# mcu_base.net
KiCad netlist of a schematic drawn in Altium Designer
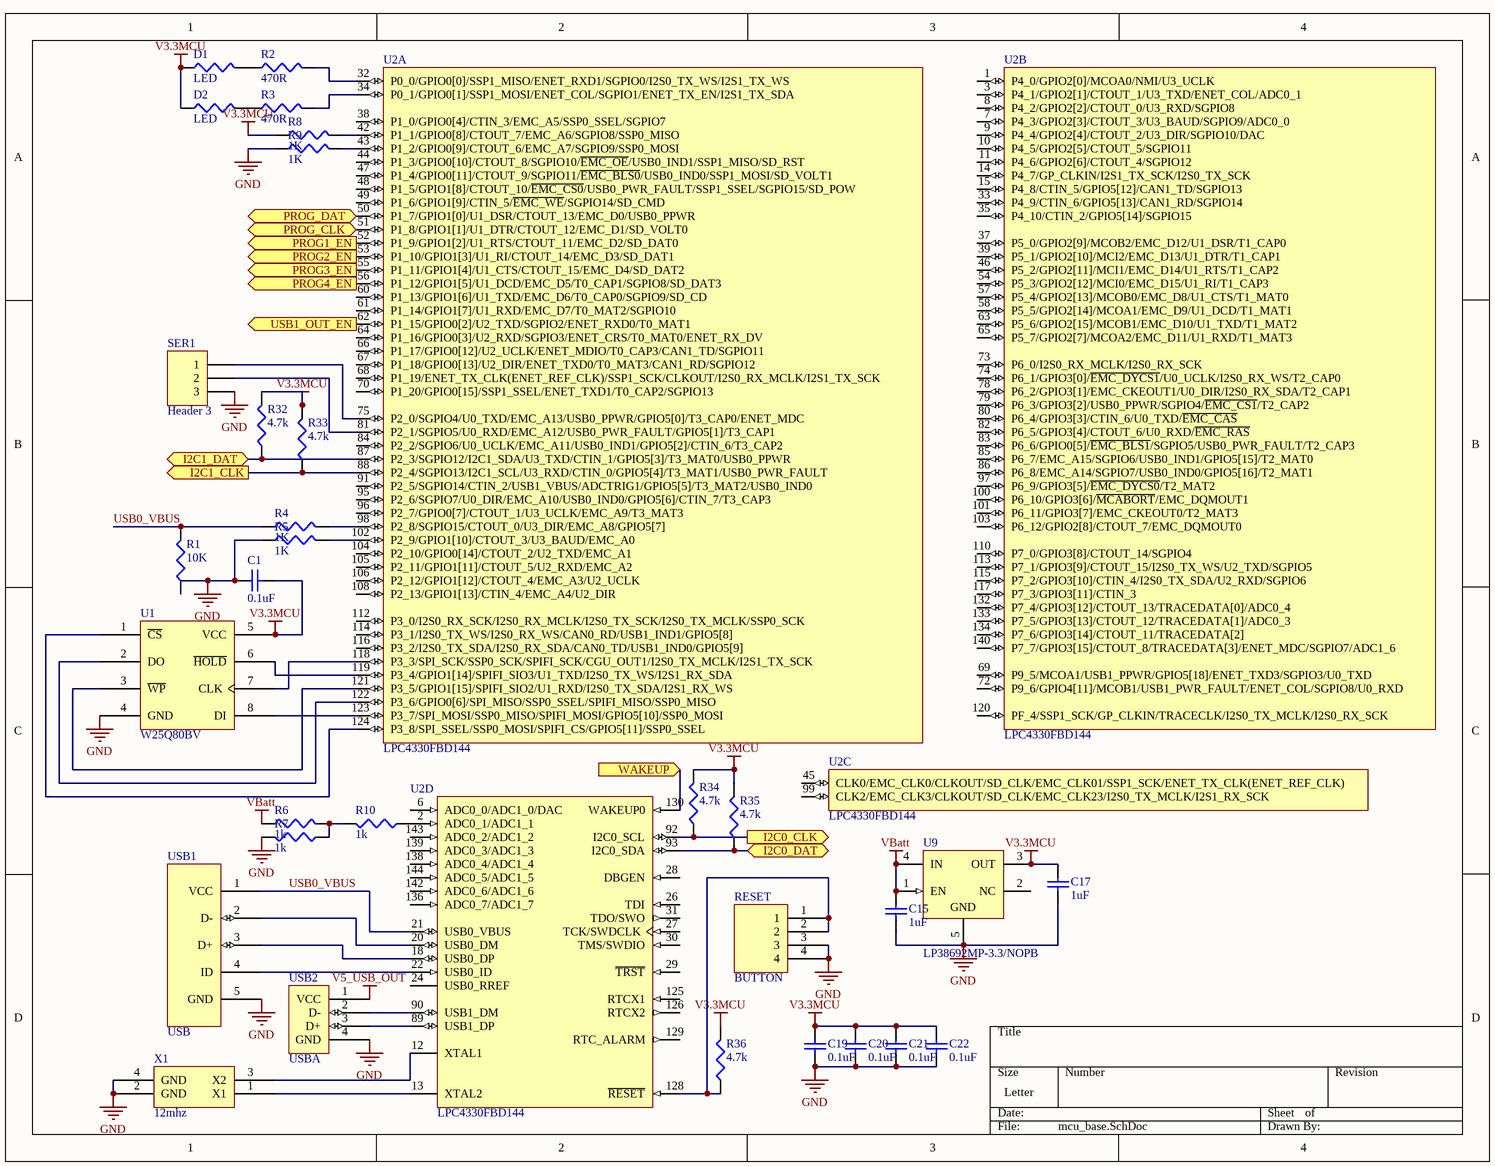
[diagram p0: mcu_base.SchDoc]

(export (version "E")
  (design (tool "Eeschema 10.0.6"))
  (components
    (comp (ref "C1")
      (value "0.1uF")
      (footprint "1608[0603]")
      (description "Capacitor (Semiconductor SIM Model)")
      (fields (field (name "PUBLISHER") "Altium Limited"))
      (libsource (lib "Miscellaneous Devices") (part "Cap Semi"))
    )
    (comp (ref "C15")
      (value "1uF")
      (footprint "1608[0603]")
      (description "Capacitor (Semiconductor SIM Model)")
      (fields (field (name "PUBLISHER") "Altium Limited"))
      (libsource (lib "Miscellaneous Devices") (part "Cap Semi"))
    )
    (comp (ref "C17")
      (value "1uF")
      (footprint "1608[0603]")
      (description "Capacitor (Semiconductor SIM Model)")
      (fields (field (name "PUBLISHER") "Altium Limited"))
      (libsource (lib "Miscellaneous Devices") (part "Cap Semi"))
    )
    (comp (ref "C19")
      (value "0.1uF")
      (footprint "1608[0603]")
      (description "Capacitor (Semiconductor SIM Model)")
      (fields (field (name "PUBLISHER") "Altium Limited"))
      (libsource (lib "Miscellaneous Devices") (part "Cap Semi"))
    )
    (comp (ref "C20")
      (value "0.1uF")
      (footprint "1608[0603]")
      (description "Capacitor (Semiconductor SIM Model)")
      (fields (field (name "PUBLISHER") "Altium Limited"))
      (libsource (lib "Miscellaneous Devices") (part "Cap Semi"))
    )
    (comp (ref "C21")
      (value "0.1uF")
      (footprint "1608[0603]")
      (description "Capacitor (Semiconductor SIM Model)")
      (fields (field (name "PUBLISHER") "Altium Limited"))
      (libsource (lib "Miscellaneous Devices") (part "Cap Semi"))
    )
    (comp (ref "C22")
      (value "0.1uF")
      (footprint "1608[0603]")
      (description "Capacitor (Semiconductor SIM Model)")
      (fields (field (name "PUBLISHER") "Altium Limited"))
      (libsource (lib "Miscellaneous Devices") (part "Cap Semi"))
    )
    (comp (ref "D1")
      (value "LED")
      (footprint "J1-0603")
      (description "Resistor")
      (fields (field (name "PUBLISHER") "Altium Limited"))
      (libsource (lib "Miscellaneous Devices") (part "Res3"))
    )
    (comp (ref "D2")
      (value "LED")
      (footprint "J1-0603")
      (description "Resistor")
      (fields (field (name "PUBLISHER") "Altium Limited"))
      (libsource (lib "Miscellaneous Devices") (part "Res3"))
    )
    (comp (ref "R1")
      (value "10K")
      (footprint "J1-0603")
      (description "Resistor")
      (fields (field (name "PUBLISHER") "Altium Limited"))
      (libsource (lib "Miscellaneous Devices") (part "Res3"))
    )
    (comp (ref "R2")
      (value "470R")
      (footprint "J1-0603")
      (description "Resistor")
      (fields (field (name "PUBLISHER") "Altium Limited"))
      (libsource (lib "Miscellaneous Devices") (part "Res3"))
    )
    (comp (ref "R3")
      (value "470R")
      (footprint "J1-0603")
      (description "Resistor")
      (fields (field (name "PUBLISHER") "Altium Limited"))
      (libsource (lib "Miscellaneous Devices") (part "Res3"))
    )
    (comp (ref "R4")
      (value "1K")
      (footprint "J1-0603")
      (description "Resistor")
      (fields (field (name "PUBLISHER") "Altium Limited"))
      (libsource (lib "Miscellaneous Devices") (part "Res3"))
    )
    (comp (ref "R5")
      (value "1K")
      (footprint "J1-0603")
      (description "Resistor")
      (fields (field (name "PUBLISHER") "Altium Limited"))
      (libsource (lib "Miscellaneous Devices") (part "Res3"))
    )
    (comp (ref "R6")
      (value "1k")
      (footprint "J1-0603")
      (description "Resistor")
      (fields (field (name "PUBLISHER") "Altium Limited"))
      (libsource (lib "Miscellaneous Devices") (part "Res3"))
    )
    (comp (ref "R7")
      (value "1k")
      (footprint "J1-0603")
      (description "Resistor")
      (fields (field (name "PUBLISHER") "Altium Limited"))
      (libsource (lib "Miscellaneous Devices") (part "Res3"))
    )
    (comp (ref "R8")
      (value "1K")
      (footprint "J1-0603")
      (description "Resistor")
      (fields (field (name "PUBLISHER") "Altium Limited"))
      (libsource (lib "Miscellaneous Devices") (part "Res3"))
    )
    (comp (ref "R9")
      (value "1K")
      (footprint "J1-0603")
      (description "Resistor")
      (fields (field (name "PUBLISHER") "Altium Limited"))
      (libsource (lib "Miscellaneous Devices") (part "Res3"))
    )
    (comp (ref "R10")
      (value "1k")
      (footprint "J1-0603")
      (description "Resistor")
      (fields (field (name "PUBLISHER") "Altium Limited"))
      (libsource (lib "Miscellaneous Devices") (part "Res3"))
    )
    (comp (ref "R32")
      (value "4.7k")
      (footprint "J1-0603")
      (description "Resistor")
      (fields (field (name "PUBLISHER") "Altium Limited"))
      (libsource (lib "Miscellaneous Devices") (part "Res3"))
    )
    (comp (ref "R33")
      (value "4.7k")
      (footprint "J1-0603")
      (description "Resistor")
      (fields (field (name "PUBLISHER") "Altium Limited"))
      (libsource (lib "Miscellaneous Devices") (part "Res3"))
    )
    (comp (ref "R34")
      (value "4.7k")
      (footprint "J1-0603")
      (description "Resistor")
      (fields (field (name "PUBLISHER") "Altium Limited"))
      (libsource (lib "Miscellaneous Devices") (part "Res3"))
    )
    (comp (ref "R35")
      (value "4.7k")
      (footprint "J1-0603")
      (description "Resistor")
      (fields (field (name "PUBLISHER") "Altium Limited"))
      (libsource (lib "Miscellaneous Devices") (part "Res3"))
    )
    (comp (ref "R36")
      (value "4.7k")
      (footprint "J1-0603")
      (description "Resistor")
      (fields (field (name "PUBLISHER") "Altium Limited"))
      (libsource (lib "Miscellaneous Devices") (part "Res3"))
    )
    (comp (ref "RESET")
      (value "BUTTON")
      (footprint "B3FS_SWITCH")
      (libsource (lib "custom_for_quadrotor") (part "BUTTON"))
    )
    (comp (ref "SER1")
      (value "Header 3")
      (footprint "HDR1X3")
      (description "Header, 3-Pin")
      (fields (field (name "PUBLISHER") "Altium Limited"))
      (libsource (lib "Miscellaneous Connectors") (part "Header 3"))
    )
    (comp (ref "U1") (value "W25Q80BV") (footprint "D8_N") (libsource (lib "KyliesParts") (part "W25Q80BV")))
    (comp (ref "U2")
      (value "LPC4330FBD144")
      (footprint "SOT486-1_V")
      (libsource (lib "NXP Semiconductors Cortex-M4") (part "LPC4330FBD144"))
    )
    (comp (ref "U9")
      (value "LP38692MP-3.3/NOPB")
      (footprint "MP05A_N")
      (fields (field (name "MANUFACTURER") "National Semiconductor"))
      (libsource (lib "National Semiconductor LDO") (part "LP38692MP-3.3/NOPB"))
    )
    (comp (ref "USB1")
      (value "USB")
      (footprint "USB/SM0.8-6H5")
      (libsource (lib "custom_for_quadrotor") (part "USB"))
    )
    (comp (ref "USB2")
      (value "USBA")
      (footprint "USB2.5-2V4A")
      (libsource (lib "custom_for_quadrotor") (part "USBA"))
    )
    (comp (ref "X1")
      (value "12mhz")
      (footprint "2SMX-3SMXB")
      (libsource (lib "KyliesParts") (part "crystal"))
    )
  )
  (nets
    (net (code "1") (name "/I2C0_CLK") (class "Default")
      (node (ref "R34") (pin "1") (pinfunction "1_1") (pintype "passive"))
      (node (ref "U2") (pin "92") (pinfunction "I2C0_SCL_92") (pintype "bidirectional"))
    )
    (net (code "2") (name "/I2C0_DAT") (class "Default")
      (node (ref "R35") (pin "1") (pinfunction "1_1") (pintype "passive"))
      (node (ref "U2") (pin "93") (pinfunction "I2C0_SDA_93") (pintype "bidirectional"))
    )
    (net (code "3") (name "/I2C1_CLK") (class "Default")
      (node (ref "R33") (pin "1") (pinfunction "1_1") (pintype "passive"))
      (node (ref "U2") (pin "88") (pinfunction "P2_4/SGPIO13/I2C1_SCL/U3_RXD/CTIN_0/GPIO5[4]/T3_MAT1/USB0_PWR_FAULT_88") (pintype "bidirectional"))
    )
    (net (code "4") (name "/I2C1_DAT") (class "Default")
      (node (ref "R32") (pin "1") (pinfunction "1_1") (pintype "passive"))
      (node (ref "U2") (pin "87") (pinfunction "P2_3/SGPIO12/I2C1_SDA/U3_TXD/CTIN_1/GPIO5[3]/T3_MAT0/USB0_PPWR_87") (pintype "bidirectional"))
    )
    (net (code "5") (name "/PROG1_EN") (class "Default")
      (node (ref "U2") (pin "52") (pinfunction "P1_9/GPIO1[2]/U1_RTS/CTOUT_11/EMC_D2/SD_DAT0_52") (pintype "bidirectional"))
    )
    (net (code "6") (name "/PROG2_EN") (class "Default")
      (node (ref "U2") (pin "53") (pinfunction "P1_10/GPIO1[3]/U1_RI/CTOUT_14/EMC_D3/SD_DAT1_53") (pintype "bidirectional"))
    )
    (net (code "7") (name "/PROG3_EN") (class "Default")
      (node (ref "U2") (pin "55") (pinfunction "P1_11/GPIO1[4]/U1_CTS/CTOUT_15/EMC_D4/SD_DAT2_55") (pintype "bidirectional"))
    )
    (net (code "8") (name "/PROG4_EN") (class "Default")
      (node (ref "U2") (pin "56") (pinfunction "P1_12/GPIO1[5]/U1_DCD/EMC_D5/T0_CAP1/SGPIO8/SD_DAT3_56") (pintype "bidirectional"))
    )
    (net (code "9") (name "/PROG_CLK") (class "Default")
      (node (ref "U2") (pin "51") (pinfunction "P1_8/GPIO1[1]/U1_DTR/CTOUT_12/EMC_D1/SD_VOLT0_51") (pintype "bidirectional"))
    )
    (net (code "10") (name "/PROG_DAT") (class "Default")
      (node (ref "U2") (pin "50") (pinfunction "P1_7/GPIO1[0]/U1_DSR/CTOUT_13/EMC_D0/USB0_PPWR_50") (pintype "bidirectional"))
    )
    (net (code "11") (name "/USB0_VBUS") (class "Default")
      (node (ref "R1") (pin "2") (pinfunction "2_2") (pintype "passive"))
      (node (ref "R4") (pin "1") (pinfunction "1_1") (pintype "passive"))
      (node (ref "U2") (pin "21") (pinfunction "USB0_VBUS_21") (pintype "bidirectional"))
      (node (ref "USB1") (pin "1") (pinfunction "VCC_1") (pintype "power_in"))
    )
    (net (code "12") (name "/USB1_OUT_EN") (class "Default")
      (node (ref "U2") (pin "62") (pinfunction "P1_15/GPIO0[2]/U2_TXD/SGPIO2/ENET_RXD0/T0_MAT1_62") (pintype "bidirectional"))
    )
    (net (code "13") (name "/WAKEUP") (class "Default")
      (node (ref "U2") (pin "130") (pinfunction "WAKEUP0_130") (pintype "input"))
    )
    (net (code "14") (name "GND") (class "Default")
      (node (ref "C1") (pin "1") (pinfunction "1_1") (pintype "passive"))
      (node (ref "C15") (pin "1") (pinfunction "1_1") (pintype "passive"))
      (node (ref "C17") (pin "1") (pinfunction "1_1") (pintype "passive"))
      (node (ref "C19") (pin "1") (pinfunction "1_1") (pintype "passive"))
      (node (ref "C20") (pin "1") (pinfunction "1_1") (pintype "passive"))
      (node (ref "C21") (pin "1") (pinfunction "1_1") (pintype "passive"))
      (node (ref "C22") (pin "1") (pinfunction "1_1") (pintype "passive"))
      (node (ref "R1") (pin "1") (pinfunction "1_1") (pintype "passive"))
      (node (ref "R5") (pin "1") (pinfunction "1_1") (pintype "passive"))
      (node (ref "R7") (pin "2") (pinfunction "2_2") (pintype "passive"))
      (node (ref "R9") (pin "1") (pinfunction "1_1") (pintype "passive"))
      (node (ref "RESET") (pin "3") (pinfunction "3_3") (pintype "passive"))
      (node (ref "RESET") (pin "4") (pinfunction "4_4") (pintype "passive"))
      (node (ref "SER1") (pin "3") (pinfunction "3_3") (pintype "passive"))
      (node (ref "U1") (pin "4") (pinfunction "GND_4") (pintype "passive"))
      (node (ref "U9") (pin "5") (pinfunction "GND_5") (pintype "power_in"))
      (node (ref "USB1") (pin "5") (pinfunction "GND_5") (pintype "power_in"))
      (node (ref "USB2") (pin "4") (pinfunction "GND_4") (pintype "power_in"))
      (node (ref "X1") (pin "2") (pinfunction "GND_2") (pintype "passive"))
      (node (ref "X1") (pin "4") (pinfunction "GND_4") (pintype "passive"))
    )
    (net (code "15") (name "Net-(D1-Pad2)") (class "Default")
      (node (ref "D1") (pin "2") (pinfunction "2_2") (pintype "passive"))
      (node (ref "R2") (pin "1") (pinfunction "1_1") (pintype "passive"))
    )
    (net (code "16") (name "Net-(D2-Pad2)") (class "Default")
      (node (ref "D2") (pin "2") (pinfunction "2_2") (pintype "passive"))
      (node (ref "R3") (pin "1") (pinfunction "1_1") (pintype "passive"))
    )
    (net (code "17") (name "Net-(R10-Pad2)") (class "Default")
      (node (ref "R10") (pin "2") (pinfunction "2_2") (pintype "passive"))
      (node (ref "R6") (pin "2") (pinfunction "2_2") (pintype "passive"))
      (node (ref "R7") (pin "1") (pinfunction "1_1") (pintype "passive"))
    )
    (net (code "18") (name "Net-(U1-CLK)") (class "Default")
      (node (ref "U1") (pin "7") (pinfunction "CLK_7") (pintype "passive"))
      (node (ref "U2") (pin "118") (pinfunction "P3_3/SPI_SCK/SSP0_SCK/SPIFI_SCK/CGU_OUT1/I2S0_TX_MCLK/I2S1_TX_SCK_118") (pintype "bidirectional"))
    )
    (net (code "19") (name "Net-(U1-CS)") (class "Default")
      (node (ref "U1") (pin "1") (pinfunction "CS_1") (pintype "passive"))
      (node (ref "U2") (pin "124") (pinfunction "P3_8/SPI_SSEL/SSP0_MOSI/SPIFI_CS/GPIO5[11]/SSP0_SSEL_124") (pintype "bidirectional"))
    )
    (net (code "20") (name "Net-(U1-DI)") (class "Default")
      (node (ref "U1") (pin "8") (pinfunction "DI_8") (pintype "passive"))
      (node (ref "U2") (pin "123") (pinfunction "P3_7/SPI_MOSI/SSP0_MISO/SPIFI_MOSI/GPIO5[10]/SSP0_MOSI_123") (pintype "bidirectional"))
    )
    (net (code "21") (name "Net-(U1-DO)") (class "Default")
      (node (ref "U1") (pin "2") (pinfunction "DO_2") (pintype "passive"))
      (node (ref "U2") (pin "122") (pinfunction "P3_6/GPIO0[6]/SPI_MISO/SSP0_SSEL/SPIFI_MISO/SSP0_MISO_122") (pintype "bidirectional"))
    )
    (net (code "22") (name "Net-(U1-HOLD)") (class "Default")
      (node (ref "U1") (pin "6") (pinfunction "HOLD_6") (pintype "passive"))
      (node (ref "U2") (pin "119") (pinfunction "P3_4/GPIO1[14]/SPIFI_SIO3/U1_TXD/I2S0_TX_WS/I2S1_RX_SDA_119") (pintype "bidirectional"))
    )
    (net (code "23") (name "Net-(U1-WP)") (class "Default")
      (node (ref "U1") (pin "3") (pinfunction "WP_3") (pintype "passive"))
      (node (ref "U2") (pin "121") (pinfunction "P3_5/GPIO1[15]/SPIFI_SIO2/U1_RXD/I2S0_TX_SDA/I2S1_RX_WS_121") (pintype "bidirectional"))
    )
    (net (code "24") (name "Net-(U2A-P0_0{slash}GPIO0[0]{slash}SSP1_MISO{slash}ENET_RXD1{slash}SGPIO0{slash}I2S0_TX_WS{slash}I2S1_TX_WS)") (class "Default")
      (node (ref "R2") (pin "2") (pinfunction "2_2") (pintype "passive"))
      (node (ref "U2") (pin "32") (pinfunction "P0_0/GPIO0[0]/SSP1_MISO/ENET_RXD1/SGPIO0/I2S0_TX_WS/I2S1_TX_WS_32") (pintype "bidirectional"))
    )
    (net (code "25") (name "Net-(U2A-P0_1{slash}GPIO0[1]{slash}SSP1_MOSI{slash}ENET_COL{slash}SGPIO1{slash}ENET_TX_EN{slash}I2S1_TX_SDA)") (class "Default")
      (node (ref "R3") (pin "2") (pinfunction "2_2") (pintype "passive"))
      (node (ref "U2") (pin "34") (pinfunction "P0_1/GPIO0[1]/SSP1_MOSI/ENET_COL/SGPIO1/ENET_TX_EN/I2S1_TX_SDA_34") (pintype "bidirectional"))
    )
    (net (code "26") (name "Net-(U2A-P1_1{slash}GPIO0[8]{slash}CTOUT_7{slash}EMC_A6{slash}SGPIO8{slash}SSP0_MISO)") (class "Default")
      (node (ref "R8") (pin "2") (pinfunction "2_2") (pintype "passive"))
      (node (ref "U2") (pin "42") (pinfunction "P1_1/GPIO0[8]/CTOUT_7/EMC_A6/SGPIO8/SSP0_MISO_42") (pintype "bidirectional"))
    )
    (net (code "27") (name "Net-(U2A-P1_2{slash}GPIO0[9]{slash}CTOUT_6{slash}EMC_A7{slash}SGPIO9{slash}SSP0_MOSI)") (class "Default")
      (node (ref "R9") (pin "2") (pinfunction "2_2") (pintype "passive"))
      (node (ref "U2") (pin "43") (pinfunction "P1_2/GPIO0[9]/CTOUT_6/EMC_A7/SGPIO9/SSP0_MOSI_43") (pintype "bidirectional"))
    )
    (net (code "28") (name "Net-(U2A-P2_0{slash}SGPIO4{slash}U0_TXD{slash}EMC_A13{slash}USB0_PPWR{slash}GPIO5[0]{slash}T3_CAP0{slash}ENET_MDC)") (class "Default")
      (node (ref "SER1") (pin "1") (pinfunction "1_1") (pintype "passive"))
      (node (ref "U2") (pin "75") (pinfunction "P2_0/SGPIO4/U0_TXD/EMC_A13/USB0_PPWR/GPIO5[0]/T3_CAP0/ENET_MDC_75") (pintype "bidirectional"))
    )
    (net (code "29") (name "Net-(U2A-P2_1{slash}SGPIO5{slash}U0_RXD{slash}EMC_A12{slash}USB0_PWR_FAULT{slash}GPIO5[1]{slash}T3_CAP1)") (class "Default")
      (node (ref "SER1") (pin "2") (pinfunction "2_2") (pintype "passive"))
      (node (ref "U2") (pin "81") (pinfunction "P2_1/SGPIO5/U0_RXD/EMC_A12/USB0_PWR_FAULT/GPIO5[1]/T3_CAP1_81") (pintype "bidirectional"))
    )
    (net (code "30") (name "Net-(U2A-P2_8{slash}SGPIO15{slash}CTOUT_0{slash}U3_DIR{slash}EMC_A8{slash}GPIO5[7])") (class "Default")
      (node (ref "R4") (pin "2") (pinfunction "2_2") (pintype "passive"))
      (node (ref "U2") (pin "98") (pinfunction "P2_8/SGPIO15/CTOUT_0/U3_DIR/EMC_A8/GPIO5[7]_98") (pintype "bidirectional"))
    )
    (net (code "31") (name "Net-(U2A-P2_9{slash}GPIO1[10]{slash}CTOUT_3{slash}U3_BAUD{slash}EMC_A0)") (class "Default")
      (node (ref "R5") (pin "2") (pinfunction "2_2") (pintype "passive"))
      (node (ref "U2") (pin "102") (pinfunction "P2_9/GPIO1[10]/CTOUT_3/U3_BAUD/EMC_A0_102") (pintype "bidirectional"))
    )
    (net (code "32") (name "Net-(U2D-ADC0_1{slash}ADC1_1)") (class "Default")
      (node (ref "R10") (pin "1") (pinfunction "1_1") (pintype "passive"))
      (node (ref "U2") (pin "2") (pinfunction "ADC0_1/ADC1_1_2") (pintype "input"))
    )
    (net (code "33") (name "Net-(U2D-USB0_DM)") (class "Default")
      (node (ref "U2") (pin "20") (pinfunction "USB0_DM_20") (pintype "bidirectional"))
      (node (ref "USB1") (pin "2") (pinfunction "D-_2") (pintype "bidirectional"))
    )
    (net (code "34") (name "Net-(U2D-USB0_DP)") (class "Default")
      (node (ref "U2") (pin "18") (pinfunction "USB0_DP_18") (pintype "bidirectional"))
      (node (ref "USB1") (pin "3") (pinfunction "D+_3") (pintype "bidirectional"))
    )
    (net (code "35") (name "Net-(U2D-USB0_ID)") (class "Default")
      (node (ref "U2") (pin "22") (pinfunction "USB0_ID_22") (pintype "input"))
      (node (ref "USB1") (pin "4") (pinfunction "ID_4") (pintype "passive"))
    )
    (net (code "36") (name "Net-(U2D-USB1_DM)") (class "Default")
      (node (ref "U2") (pin "90") (pinfunction "USB1_DM_90") (pintype "bidirectional"))
      (node (ref "USB2") (pin "2") (pinfunction "D-_2") (pintype "bidirectional"))
    )
    (net (code "37") (name "Net-(U2D-USB1_DP)") (class "Default")
      (node (ref "U2") (pin "89") (pinfunction "USB1_DP_89") (pintype "bidirectional"))
      (node (ref "USB2") (pin "3") (pinfunction "D+_3") (pintype "bidirectional"))
    )
    (net (code "38") (name "Net-(U2D-XTAL1)") (class "Default")
      (node (ref "U2") (pin "12") (pinfunction "XTAL1_12") (pintype "passive"))
      (node (ref "X1") (pin "3") (pinfunction "X2_3") (pintype "passive"))
    )
    (net (code "39") (name "Net-(U2D-XTAL2)") (class "Default")
      (node (ref "U2") (pin "13") (pinfunction "XTAL2_13") (pintype "passive"))
      (node (ref "X1") (pin "1") (pinfunction "X1_1") (pintype "passive"))
    )
    (net (code "40") (name "Net-(U2D-~{RESET})") (class "Default")
      (node (ref "R36") (pin "1") (pinfunction "1_1") (pintype "passive"))
      (node (ref "RESET") (pin "1") (pinfunction "1_1") (pintype "passive"))
      (node (ref "RESET") (pin "2") (pinfunction "2_2") (pintype "passive"))
      (node (ref "U2") (pin "128") (pinfunction "~{RESET}_128") (pintype "input"))
    )
    (net (code "41") (name "V3.3MCU") (class "Default")
      (node (ref "C1") (pin "2") (pinfunction "2_2") (pintype "passive"))
      (node (ref "C17") (pin "2") (pinfunction "2_2") (pintype "passive"))
      (node (ref "C19") (pin "2") (pinfunction "2_2") (pintype "passive"))
      (node (ref "C20") (pin "2") (pinfunction "2_2") (pintype "passive"))
      (node (ref "C21") (pin "2") (pinfunction "2_2") (pintype "passive"))
      (node (ref "C22") (pin "2") (pinfunction "2_2") (pintype "passive"))
      (node (ref "D1") (pin "1") (pinfunction "1_1") (pintype "passive"))
      (node (ref "D2") (pin "1") (pinfunction "1_1") (pintype "passive"))
      (node (ref "R32") (pin "2") (pinfunction "2_2") (pintype "passive"))
      (node (ref "R33") (pin "2") (pinfunction "2_2") (pintype "passive"))
      (node (ref "R34") (pin "2") (pinfunction "2_2") (pintype "passive"))
      (node (ref "R35") (pin "2") (pinfunction "2_2") (pintype "passive"))
      (node (ref "R36") (pin "2") (pinfunction "2_2") (pintype "passive"))
      (node (ref "R8") (pin "1") (pinfunction "1_1") (pintype "passive"))
      (node (ref "U1") (pin "5") (pinfunction "VCC_5") (pintype "passive"))
      (node (ref "U9") (pin "3") (pinfunction "OUT_3") (pintype "power_in"))
    )
    (net (code "42") (name "V5_USB_OUT") (class "Default")
      (node (ref "USB2") (pin "1") (pinfunction "VCC_1") (pintype "power_in"))
    )
    (net (code "43") (name "VBatt") (class "Default")
      (node (ref "C15") (pin "2") (pinfunction "2_2") (pintype "passive"))
      (node (ref "R6") (pin "1") (pinfunction "1_1") (pintype "passive"))
      (node (ref "U9") (pin "1") (pinfunction "EN_1") (pintype "input"))
      (node (ref "U9") (pin "4") (pinfunction "IN_4") (pintype "power_in"))
    )
    (net (code "44") (name "unconnected-(U2A-P1_0{slash}GPIO0[4]{slash}CTIN_3{slash}EMC_A5{slash}SSP0_SSEL{slash}SGPIO7-Pad38)") (class "Default")
      (node (ref "U2") (pin "38") (pinfunction "P1_0/GPIO0[4]/CTIN_3/EMC_A5/SSP0_SSEL/SGPIO7_38") (pintype "bidirectional"))
    )
    (net (code "45") (name "unconnected-(U2A-P1_3{slash}GPIO0[10]{slash}CTOUT_8{slash}SGPIO10{slash}~{EMC_OE}{slash}USB0_IND1{slash}SSP1_MISO{slash}SD_RST-Pad44)") (class "Default")
      (node (ref "U2") (pin "44") (pinfunction "P1_3/GPIO0[10]/CTOUT_8/SGPIO10/~{EMC_OE}/USB0_IND1/SSP1_MISO/SD_RST_44") (pintype "bidirectional"))
    )
    (net (code "46") (name "unconnected-(U2A-P1_4{slash}GPIO0[11]{slash}CTOUT_9{slash}SGPIO11{slash}~{EMC_BLS0}{slash}USB0_IND0{slash}SSP1_MOSI{slash}SD_VOLT1-Pad47)") (class "Default")
      (node (ref "U2") (pin "47") (pinfunction "P1_4/GPIO0[11]/CTOUT_9/SGPIO11/~{EMC_BLS0}/USB0_IND0/SSP1_MOSI/SD_VOLT1_47") (pintype "bidirectional"))
    )
    (net (code "47") (name "unconnected-(U2A-P1_5{slash}GPIO1[8]{slash}CTOUT_10{slash}~{EMC_CS0}{slash}USB0_PWR_FAULT{slash}SSP1_SSEL{slash}SGPIO15{slash}SD_POW-Pad48)") (class "Default")
      (node (ref "U2") (pin "48") (pinfunction "P1_5/GPIO1[8]/CTOUT_10/~{EMC_CS0}/USB0_PWR_FAULT/SSP1_SSEL/SGPIO15/SD_POW_48") (pintype "bidirectional"))
    )
    (net (code "48") (name "unconnected-(U2A-P1_6{slash}GPIO1[9]{slash}CTIN_5{slash}~{EMC_WE}{slash}SGPIO14{slash}SD_CMD-Pad49)") (class "Default")
      (node (ref "U2") (pin "49") (pinfunction "P1_6/GPIO1[9]/CTIN_5/~{EMC_WE}/SGPIO14/SD_CMD_49") (pintype "bidirectional"))
    )
    (net (code "49") (name "unconnected-(U2A-P1_13{slash}GPIO1[6]{slash}U1_TXD{slash}EMC_D6{slash}T0_CAP0{slash}SGPIO9{slash}SD_CD-Pad60)") (class "Default")
      (node (ref "U2") (pin "60") (pinfunction "P1_13/GPIO1[6]/U1_TXD/EMC_D6/T0_CAP0/SGPIO9/SD_CD_60") (pintype "bidirectional"))
    )
    (net (code "50") (name "unconnected-(U2A-P1_14{slash}GPIO1[7]{slash}U1_RXD{slash}EMC_D7{slash}T0_MAT2{slash}SGPIO10-Pad61)") (class "Default")
      (node (ref "U2") (pin "61") (pinfunction "P1_14/GPIO1[7]/U1_RXD/EMC_D7/T0_MAT2/SGPIO10_61") (pintype "bidirectional"))
    )
    (net (code "51") (name "unconnected-(U2A-P1_16{slash}GPIO0[3]{slash}U2_RXD{slash}SGPIO3{slash}ENET_CRS{slash}T0_MAT0{slash}ENET_RX_DV-Pad64)") (class "Default")
      (node (ref "U2") (pin "64") (pinfunction "P1_16/GPIO0[3]/U2_RXD/SGPIO3/ENET_CRS/T0_MAT0/ENET_RX_DV_64") (pintype "bidirectional"))
    )
    (net (code "52") (name "unconnected-(U2A-P1_17{slash}GPIO0[12]{slash}U2_UCLK{slash}ENET_MDIO{slash}T0_CAP3{slash}CAN1_TD{slash}SGPIO11-Pad66)") (class "Default")
      (node (ref "U2") (pin "66") (pinfunction "P1_17/GPIO0[12]/U2_UCLK/ENET_MDIO/T0_CAP3/CAN1_TD/SGPIO11_66") (pintype "bidirectional"))
    )
    (net (code "53") (name "unconnected-(U2A-P1_18{slash}GPIO0[13]{slash}U2_DIR{slash}ENET_TXD0{slash}T0_MAT3{slash}CAN1_RD{slash}SGPIO12-Pad67)") (class "Default")
      (node (ref "U2") (pin "67") (pinfunction "P1_18/GPIO0[13]/U2_DIR/ENET_TXD0/T0_MAT3/CAN1_RD/SGPIO12_67") (pintype "bidirectional"))
    )
    (net (code "54") (name "unconnected-(U2A-P1_19{slash}ENET_TX_CLK(ENET_REF_CLK){slash}SSP1_SCK{slash}CLKOUT{slash}I2S0_RX_MCLK{slash}I2S1_TX_SCK-Pad68)") (class "Default")
      (node (ref "U2") (pin "68") (pinfunction "P1_19/ENET_TX_CLK(ENET_REF_CLK)/SSP1_SCK/CLKOUT/I2S0_RX_MCLK/I2S1_TX_SCK_68") (pintype "bidirectional"))
    )
    (net (code "55") (name "unconnected-(U2A-P1_20{slash}GPIO0[15]{slash}SSP1_SSEL{slash}ENET_TXD1{slash}T0_CAP2{slash}SGPIO13-Pad70)") (class "Default")
      (node (ref "U2") (pin "70") (pinfunction "P1_20/GPIO0[15]/SSP1_SSEL/ENET_TXD1/T0_CAP2/SGPIO13_70") (pintype "bidirectional"))
    )
    (net (code "56") (name "unconnected-(U2A-P2_2{slash}SGPIO6{slash}U0_UCLK{slash}EMC_A11{slash}USB0_IND1{slash}GPIO5[2]{slash}CTIN_6{slash}T3_CAP2-Pad84)") (class "Default")
      (node (ref "U2") (pin "84") (pinfunction "P2_2/SGPIO6/U0_UCLK/EMC_A11/USB0_IND1/GPIO5[2]/CTIN_6/T3_CAP2_84") (pintype "bidirectional"))
    )
    (net (code "57") (name "unconnected-(U2A-P2_5{slash}SGPIO14{slash}CTIN_2{slash}USB1_VBUS{slash}ADCTRIG1{slash}GPIO5[5]{slash}T3_MAT2{slash}USB0_IND0-Pad91)") (class "Default")
      (node (ref "U2") (pin "91") (pinfunction "P2_5/SGPIO14/CTIN_2/USB1_VBUS/ADCTRIG1/GPIO5[5]/T3_MAT2/USB0_IND0_91") (pintype "bidirectional"))
    )
    (net (code "58") (name "unconnected-(U2A-P2_6{slash}SGPIO7{slash}U0_DIR{slash}EMC_A10{slash}USB0_IND0{slash}GPIO5[6]{slash}CTIN_7{slash}T3_CAP3-Pad95)") (class "Default")
      (node (ref "U2") (pin "95") (pinfunction "P2_6/SGPIO7/U0_DIR/EMC_A10/USB0_IND0/GPIO5[6]/CTIN_7/T3_CAP3_95") (pintype "bidirectional"))
    )
    (net (code "59") (name "unconnected-(U2A-P2_7{slash}GPIO0[7]{slash}CTOUT_1{slash}U3_UCLK{slash}EMC_A9{slash}T3_MAT3-Pad96)") (class "Default")
      (node (ref "U2") (pin "96") (pinfunction "P2_7/GPIO0[7]/CTOUT_1/U3_UCLK/EMC_A9/T3_MAT3_96") (pintype "bidirectional"))
    )
    (net (code "60") (name "unconnected-(U2A-P2_10{slash}GPIO0[14]{slash}CTOUT_2{slash}U2_TXD{slash}EMC_A1-Pad104)") (class "Default")
      (node (ref "U2") (pin "104") (pinfunction "P2_10/GPIO0[14]/CTOUT_2/U2_TXD/EMC_A1_104") (pintype "bidirectional"))
    )
    (net (code "61") (name "unconnected-(U2A-P2_11{slash}GPIO1[11]{slash}CTOUT_5{slash}U2_RXD{slash}EMC_A2-Pad105)") (class "Default")
      (node (ref "U2") (pin "105") (pinfunction "P2_11/GPIO1[11]/CTOUT_5/U2_RXD/EMC_A2_105") (pintype "bidirectional"))
    )
    (net (code "62") (name "unconnected-(U2A-P2_12{slash}GPIO1[12]{slash}CTOUT_4{slash}EMC_A3{slash}U2_UCLK-Pad106)") (class "Default")
      (node (ref "U2") (pin "106") (pinfunction "P2_12/GPIO1[12]/CTOUT_4/EMC_A3/U2_UCLK_106") (pintype "bidirectional"))
    )
    (net (code "63") (name "unconnected-(U2A-P2_13{slash}GPIO1[13]{slash}CTIN_4{slash}EMC_A4{slash}U2_DIR-Pad108)") (class "Default")
      (node (ref "U2") (pin "108") (pinfunction "P2_13/GPIO1[13]/CTIN_4/EMC_A4/U2_DIR_108") (pintype "bidirectional"))
    )
    (net (code "64") (name "unconnected-(U2A-P3_0{slash}I2S0_RX_SCK{slash}I2S0_RX_MCLK{slash}I2S0_TX_SCK{slash}I2S0_TX_MCLK{slash}SSP0_SCK-Pad112)") (class "Default")
      (node (ref "U2") (pin "112") (pinfunction "P3_0/I2S0_RX_SCK/I2S0_RX_MCLK/I2S0_TX_SCK/I2S0_TX_MCLK/SSP0_SCK_112") (pintype "bidirectional"))
    )
    (net (code "65") (name "unconnected-(U2A-P3_1{slash}I2S0_TX_WS{slash}I2S0_RX_WS{slash}CAN0_RD{slash}USB1_IND1{slash}GPIO5[8]-Pad114)") (class "Default")
      (node (ref "U2") (pin "114") (pinfunction "P3_1/I2S0_TX_WS/I2S0_RX_WS/CAN0_RD/USB1_IND1/GPIO5[8]_114") (pintype "bidirectional"))
    )
    (net (code "66") (name "unconnected-(U2A-P3_2{slash}I2S0_TX_SDA{slash}I2S0_RX_SDA{slash}CAN0_TD{slash}USB1_IND0{slash}GPIO5[9]-Pad116)") (class "Default")
      (node (ref "U2") (pin "116") (pinfunction "P3_2/I2S0_TX_SDA/I2S0_RX_SDA/CAN0_TD/USB1_IND0/GPIO5[9]_116") (pintype "bidirectional"))
    )
    (net (code "67") (name "unconnected-(U2B-P4_0{slash}GPIO2[0]{slash}MCOA0{slash}NMI{slash}U3_UCLK-Pad1)") (class "Default")
      (node (ref "U2") (pin "1") (pinfunction "P4_0/GPIO2[0]/MCOA0/NMI/U3_UCLK_1") (pintype "bidirectional"))
    )
    (net (code "68") (name "unconnected-(U2B-P4_1{slash}GPIO2[1]{slash}CTOUT_1{slash}U3_TXD{slash}ENET_COL{slash}ADC0_1-Pad3)") (class "Default")
      (node (ref "U2") (pin "3") (pinfunction "P4_1/GPIO2[1]/CTOUT_1/U3_TXD/ENET_COL/ADC0_1_3") (pintype "bidirectional"))
    )
    (net (code "69") (name "unconnected-(U2B-P4_2{slash}GPIO2[2]{slash}CTOUT_0{slash}U3_RXD{slash}SGPIO8-Pad8)") (class "Default")
      (node (ref "U2") (pin "8") (pinfunction "P4_2/GPIO2[2]/CTOUT_0/U3_RXD/SGPIO8_8") (pintype "bidirectional"))
    )
    (net (code "70") (name "unconnected-(U2B-P4_3{slash}GPIO2[3]{slash}CTOUT_3{slash}U3_BAUD{slash}SGPIO9{slash}ADC0_0-Pad7)") (class "Default")
      (node (ref "U2") (pin "7") (pinfunction "P4_3/GPIO2[3]/CTOUT_3/U3_BAUD/SGPIO9/ADC0_0_7") (pintype "bidirectional"))
    )
    (net (code "71") (name "unconnected-(U2B-P4_4{slash}GPIO2[4]{slash}CTOUT_2{slash}U3_DIR{slash}SGPIO10{slash}DAC-Pad9)") (class "Default")
      (node (ref "U2") (pin "9") (pinfunction "P4_4/GPIO2[4]/CTOUT_2/U3_DIR/SGPIO10/DAC_9") (pintype "bidirectional"))
    )
    (net (code "72") (name "unconnected-(U2B-P4_5{slash}GPIO2[5]{slash}CTOUT_5{slash}SGPIO11-Pad10)") (class "Default")
      (node (ref "U2") (pin "10") (pinfunction "P4_5/GPIO2[5]/CTOUT_5/SGPIO11_10") (pintype "bidirectional"))
    )
    (net (code "73") (name "unconnected-(U2B-P4_6{slash}GPIO2[6]{slash}CTOUT_4{slash}SGPIO12-Pad11)") (class "Default")
      (node (ref "U2") (pin "11") (pinfunction "P4_6/GPIO2[6]/CTOUT_4/SGPIO12_11") (pintype "bidirectional"))
    )
    (net (code "74") (name "unconnected-(U2B-P4_7{slash}GP_CLKIN{slash}I2S1_TX_SCK{slash}I2S0_TX_SCK-Pad14)") (class "Default")
      (node (ref "U2") (pin "14") (pinfunction "P4_7/GP_CLKIN/I2S1_TX_SCK/I2S0_TX_SCK_14") (pintype "bidirectional"))
    )
    (net (code "75") (name "unconnected-(U2B-P4_8{slash}CTIN_5{slash}GPIO5[12]{slash}CAN1_TD{slash}SGPIO13-Pad15)") (class "Default")
      (node (ref "U2") (pin "15") (pinfunction "P4_8/CTIN_5/GPIO5[12]/CAN1_TD/SGPIO13_15") (pintype "bidirectional"))
    )
    (net (code "76") (name "unconnected-(U2B-P4_9{slash}CTIN_6{slash}GPIO5[13]{slash}CAN1_RD{slash}SGPIO14-Pad33)") (class "Default")
      (node (ref "U2") (pin "33") (pinfunction "P4_9/CTIN_6/GPIO5[13]/CAN1_RD/SGPIO14_33") (pintype "bidirectional"))
    )
    (net (code "77") (name "unconnected-(U2B-P4_10{slash}CTIN_2{slash}GPIO5[14]{slash}SGPIO15-Pad35)") (class "Default")
      (node (ref "U2") (pin "35") (pinfunction "P4_10/CTIN_2/GPIO5[14]/SGPIO15_35") (pintype "bidirectional"))
    )
    (net (code "78") (name "unconnected-(U2B-P5_0{slash}GPIO2[9]{slash}MCOB2{slash}EMC_D12{slash}U1_DSR{slash}T1_CAP0-Pad37)") (class "Default")
      (node (ref "U2") (pin "37") (pinfunction "P5_0/GPIO2[9]/MCOB2/EMC_D12/U1_DSR/T1_CAP0_37") (pintype "bidirectional"))
    )
    (net (code "79") (name "unconnected-(U2B-P5_1{slash}GPIO2[10]{slash}MCI2{slash}EMC_D13{slash}U1_DTR{slash}T1_CAP1-Pad39)") (class "Default")
      (node (ref "U2") (pin "39") (pinfunction "P5_1/GPIO2[10]/MCI2/EMC_D13/U1_DTR/T1_CAP1_39") (pintype "bidirectional"))
    )
    (net (code "80") (name "unconnected-(U2B-P5_2{slash}GPIO2[11]{slash}MCI1{slash}EMC_D14{slash}U1_RTS{slash}T1_CAP2-Pad46)") (class "Default")
      (node (ref "U2") (pin "46") (pinfunction "P5_2/GPIO2[11]/MCI1/EMC_D14/U1_RTS/T1_CAP2_46") (pintype "bidirectional"))
    )
    (net (code "81") (name "unconnected-(U2B-P5_3{slash}GPIO2[12]{slash}MCI0{slash}EMC_D15{slash}U1_RI{slash}T1_CAP3-Pad54)") (class "Default")
      (node (ref "U2") (pin "54") (pinfunction "P5_3/GPIO2[12]/MCI0/EMC_D15/U1_RI/T1_CAP3_54") (pintype "bidirectional"))
    )
    (net (code "82") (name "unconnected-(U2B-P5_4{slash}GPIO2[13]{slash}MCOB0{slash}EMC_D8{slash}U1_CTS{slash}T1_MAT0-Pad57)") (class "Default")
      (node (ref "U2") (pin "57") (pinfunction "P5_4/GPIO2[13]/MCOB0/EMC_D8/U1_CTS/T1_MAT0_57") (pintype "bidirectional"))
    )
    (net (code "83") (name "unconnected-(U2B-P5_5{slash}GPIO2[14]{slash}MCOA1{slash}EMC_D9{slash}U1_DCD{slash}T1_MAT1-Pad58)") (class "Default")
      (node (ref "U2") (pin "58") (pinfunction "P5_5/GPIO2[14]/MCOA1/EMC_D9/U1_DCD/T1_MAT1_58") (pintype "bidirectional"))
    )
    (net (code "84") (name "unconnected-(U2B-P5_6{slash}GPIO2[15]{slash}MCOB1{slash}EMC_D10{slash}U1_TXD{slash}T1_MAT2-Pad63)") (class "Default")
      (node (ref "U2") (pin "63") (pinfunction "P5_6/GPIO2[15]/MCOB1/EMC_D10/U1_TXD/T1_MAT2_63") (pintype "bidirectional"))
    )
    (net (code "85") (name "unconnected-(U2B-P5_7{slash}GPIO2[7]{slash}MCOA2{slash}EMC_D11{slash}U1_RXD{slash}T1_MAT3-Pad65)") (class "Default")
      (node (ref "U2") (pin "65") (pinfunction "P5_7/GPIO2[7]/MCOA2/EMC_D11/U1_RXD/T1_MAT3_65") (pintype "bidirectional"))
    )
    (net (code "86") (name "unconnected-(U2B-P6_0{slash}I2S0_RX_MCLK{slash}I2S0_RX_SCK-Pad73)") (class "Default")
      (node (ref "U2") (pin "73") (pinfunction "P6_0/I2S0_RX_MCLK/I2S0_RX_SCK_73") (pintype "bidirectional"))
    )
    (net (code "87") (name "unconnected-(U2B-P6_1{slash}GPIO3[0]{slash}~{EMC_DYCS1}{slash}U0_UCLK{slash}I2S0_RX_WS{slash}T2_CAP0-Pad74)") (class "Default")
      (node (ref "U2") (pin "74") (pinfunction "P6_1/GPIO3[0]/~{EMC_DYCS1}/U0_UCLK/I2S0_RX_WS/T2_CAP0_74") (pintype "bidirectional"))
    )
    (net (code "88") (name "unconnected-(U2B-P6_2{slash}GPIO3[1]{slash}EMC_CKEOUT1{slash}U0_DIR{slash}I2S0_RX_SDA{slash}T2_CAP1-Pad78)") (class "Default")
      (node (ref "U2") (pin "78") (pinfunction "P6_2/GPIO3[1]/EMC_CKEOUT1/U0_DIR/I2S0_RX_SDA/T2_CAP1_78") (pintype "bidirectional"))
    )
    (net (code "89") (name "unconnected-(U2B-P6_3{slash}GPIO3[2]{slash}USB0_PPWR{slash}SGPIO4{slash}~{EMC_CS1}{slash}T2_CAP2-Pad79)") (class "Default")
      (node (ref "U2") (pin "79") (pinfunction "P6_3/GPIO3[2]/USB0_PPWR/SGPIO4/~{EMC_CS1}/T2_CAP2_79") (pintype "bidirectional"))
    )
    (net (code "90") (name "unconnected-(U2B-P6_4{slash}GPIO3[3]{slash}CTIN_6{slash}U0_TXD{slash}~{EMC_CAS}-Pad80)") (class "Default")
      (node (ref "U2") (pin "80") (pinfunction "P6_4/GPIO3[3]/CTIN_6/U0_TXD/~{EMC_CAS}_80") (pintype "bidirectional"))
    )
    (net (code "91") (name "unconnected-(U2B-P6_5{slash}GPIO3[4]{slash}CTOUT_6{slash}U0_RXD{slash}~{EMC_RAS}-Pad82)") (class "Default")
      (node (ref "U2") (pin "82") (pinfunction "P6_5/GPIO3[4]/CTOUT_6/U0_RXD/~{EMC_RAS}_82") (pintype "bidirectional"))
    )
    (net (code "92") (name "unconnected-(U2B-P6_6{slash}GPIO0[5]{slash}~{EMC_BLS1}{slash}SGPIO5{slash}USB0_PWR_FAULT{slash}T2_CAP3-Pad83)") (class "Default")
      (node (ref "U2") (pin "83") (pinfunction "P6_6/GPIO0[5]/~{EMC_BLS1}/SGPIO5/USB0_PWR_FAULT/T2_CAP3_83") (pintype "bidirectional"))
    )
    (net (code "93") (name "unconnected-(U2B-P6_7{slash}EMC_A15{slash}SGPIO6{slash}USB0_IND1{slash}GPIO5[15]{slash}T2_MAT0-Pad85)") (class "Default")
      (node (ref "U2") (pin "85") (pinfunction "P6_7/EMC_A15/SGPIO6/USB0_IND1/GPIO5[15]/T2_MAT0_85") (pintype "bidirectional"))
    )
    (net (code "94") (name "unconnected-(U2B-P6_8{slash}EMC_A14{slash}SGPIO7{slash}USB0_IND0{slash}GPIO5[16]{slash}T2_MAT1-Pad86)") (class "Default")
      (node (ref "U2") (pin "86") (pinfunction "P6_8/EMC_A14/SGPIO7/USB0_IND0/GPIO5[16]/T2_MAT1_86") (pintype "bidirectional"))
    )
    (net (code "95") (name "unconnected-(U2B-P6_9{slash}GPIO3[5]{slash}~{EMC_DYCS0}{slash}T2_MAT2-Pad97)") (class "Default")
      (node (ref "U2") (pin "97") (pinfunction "P6_9/GPIO3[5]/~{EMC_DYCS0}/T2_MAT2_97") (pintype "bidirectional"))
    )
    (net (code "96") (name "unconnected-(U2B-P6_10{slash}GPIO3[6]{slash}~{MCABORT}{slash}EMC_DQMOUT1-Pad100)") (class "Default")
      (node (ref "U2") (pin "100") (pinfunction "P6_10/GPIO3[6]/~{MCABORT}/EMC_DQMOUT1_100") (pintype "bidirectional"))
    )
    (net (code "97") (name "unconnected-(U2B-P6_11{slash}GPIO3[7]{slash}EMC_CKEOUT0{slash}T2_MAT3-Pad101)") (class "Default")
      (node (ref "U2") (pin "101") (pinfunction "P6_11/GPIO3[7]/EMC_CKEOUT0/T2_MAT3_101") (pintype "bidirectional"))
    )
    (net (code "98") (name "unconnected-(U2B-P6_12{slash}GPIO2[8]{slash}CTOUT_7{slash}EMC_DQMOUT0-Pad103)") (class "Default")
      (node (ref "U2") (pin "103") (pinfunction "P6_12/GPIO2[8]/CTOUT_7/EMC_DQMOUT0_103") (pintype "bidirectional"))
    )
    (net (code "99") (name "unconnected-(U2B-P7_0{slash}GPIO3[8]{slash}CTOUT_14{slash}SGPIO4-Pad110)") (class "Default")
      (node (ref "U2") (pin "110") (pinfunction "P7_0/GPIO3[8]/CTOUT_14/SGPIO4_110") (pintype "bidirectional"))
    )
    (net (code "100") (name "unconnected-(U2B-P7_1{slash}GPIO3[9]{slash}CTOUT_15{slash}I2S0_TX_WS{slash}U2_TXD{slash}SGPIO5-Pad113)") (class "Default")
      (node (ref "U2") (pin "113") (pinfunction "P7_1/GPIO3[9]/CTOUT_15/I2S0_TX_WS/U2_TXD/SGPIO5_113") (pintype "bidirectional"))
    )
    (net (code "101") (name "unconnected-(U2B-P7_2{slash}GPIO3[10]{slash}CTIN_4{slash}I2S0_TX_SDA{slash}U2_RXD{slash}SGPIO6-Pad115)") (class "Default")
      (node (ref "U2") (pin "115") (pinfunction "P7_2/GPIO3[10]/CTIN_4/I2S0_TX_SDA/U2_RXD/SGPIO6_115") (pintype "bidirectional"))
    )
    (net (code "102") (name "unconnected-(U2B-P7_3{slash}GPIO3[11]{slash}CTIN_3-Pad117)") (class "Default")
      (node (ref "U2") (pin "117") (pinfunction "P7_3/GPIO3[11]/CTIN_3_117") (pintype "bidirectional"))
    )
    (net (code "103") (name "unconnected-(U2B-P7_4{slash}GPIO3[12]{slash}CTOUT_13{slash}TRACEDATA[0]{slash}ADC0_4-Pad132)") (class "Default")
      (node (ref "U2") (pin "132") (pinfunction "P7_4/GPIO3[12]/CTOUT_13/TRACEDATA[0]/ADC0_4_132") (pintype "bidirectional"))
    )
    (net (code "104") (name "unconnected-(U2B-P7_5{slash}GPIO3[13]{slash}CTOUT_12{slash}TRACEDATA[1]{slash}ADC0_3-Pad133)") (class "Default")
      (node (ref "U2") (pin "133") (pinfunction "P7_5/GPIO3[13]/CTOUT_12/TRACEDATA[1]/ADC0_3_133") (pintype "bidirectional"))
    )
    (net (code "105") (name "unconnected-(U2B-P7_6{slash}GPIO3[14]{slash}CTOUT_11{slash}TRACEDATA[2]-Pad134)") (class "Default")
      (node (ref "U2") (pin "134") (pinfunction "P7_6/GPIO3[14]/CTOUT_11/TRACEDATA[2]_134") (pintype "bidirectional"))
    )
    (net (code "106") (name "unconnected-(U2B-P7_7{slash}GPIO3[15]{slash}CTOUT_8{slash}TRACEDATA[3]{slash}ENET_MDC{slash}SGPIO7{slash}ADC1_6-Pad140)") (class "Default")
      (node (ref "U2") (pin "140") (pinfunction "P7_7/GPIO3[15]/CTOUT_8/TRACEDATA[3]/ENET_MDC/SGPIO7/ADC1_6_140") (pintype "bidirectional"))
    )
    (net (code "107") (name "unconnected-(U2B-P9_5{slash}MCOA1{slash}USB1_PPWR{slash}GPIO5[18]{slash}ENET_TXD3{slash}SGPIO3{slash}U0_TXD-Pad69)") (class "Default")
      (node (ref "U2") (pin "69") (pinfunction "P9_5/MCOA1/USB1_PPWR/GPIO5[18]/ENET_TXD3/SGPIO3/U0_TXD_69") (pintype "bidirectional"))
    )
    (net (code "108") (name "unconnected-(U2B-P9_6{slash}GPIO4[11]{slash}MCOB1{slash}USB1_PWR_FAULT{slash}ENET_COL{slash}SGPIO8{slash}U0_RXD-Pad72)") (class "Default")
      (node (ref "U2") (pin "72") (pinfunction "P9_6/GPIO4[11]/MCOB1/USB1_PWR_FAULT/ENET_COL/SGPIO8/U0_RXD_72") (pintype "bidirectional"))
    )
    (net (code "109") (name "unconnected-(U2B-PF_4{slash}SSP1_SCK{slash}GP_CLKIN{slash}TRACECLK{slash}I2S0_TX_MCLK{slash}I2S0_RX_SCK-Pad120)") (class "Default")
      (node (ref "U2") (pin "120") (pinfunction "PF_4/SSP1_SCK/GP_CLKIN/TRACECLK/I2S0_TX_MCLK/I2S0_RX_SCK_120") (pintype "bidirectional"))
    )
    (net (code "110") (name "unconnected-(U2C-CLK0{slash}EMC_CLK0{slash}CLKOUT{slash}SD_CLK{slash}EMC_CLK01{slash}SSP1_SCK{slash}ENET_TX_CLK(ENET_REF_CLK)-Pad45)") (class "Default")
      (node (ref "U2") (pin "45") (pinfunction "CLK0/EMC_CLK0/CLKOUT/SD_CLK/EMC_CLK01/SSP1_SCK/ENET_TX_CLK(ENET_REF_CLK)_45") (pintype "bidirectional"))
    )
    (net (code "111") (name "unconnected-(U2C-CLK2{slash}EMC_CLK3{slash}CLKOUT{slash}SD_CLK{slash}EMC_CLK23{slash}I2S0_TX_MCLK{slash}I2S1_RX_SCK-Pad99)") (class "Default")
      (node (ref "U2") (pin "99") (pinfunction "CLK2/EMC_CLK3/CLKOUT/SD_CLK/EMC_CLK23/I2S0_TX_MCLK/I2S1_RX_SCK_99") (pintype "bidirectional"))
    )
    (net (code "112") (name "unconnected-(U2D-ADC0_0{slash}ADC1_0{slash}DAC-Pad6)") (class "Default")
      (node (ref "U2") (pin "6") (pinfunction "ADC0_0/ADC1_0/DAC_6") (pintype "input"))
    )
    (net (code "113") (name "unconnected-(U2D-ADC0_2{slash}ADC1_2-Pad143)") (class "Default")
      (node (ref "U2") (pin "143") (pinfunction "ADC0_2/ADC1_2_143") (pintype "input"))
    )
    (net (code "114") (name "unconnected-(U2D-ADC0_3{slash}ADC1_3-Pad139)") (class "Default")
      (node (ref "U2") (pin "139") (pinfunction "ADC0_3/ADC1_3_139") (pintype "input"))
    )
    (net (code "115") (name "unconnected-(U2D-ADC0_4{slash}ADC1_4-Pad138)") (class "Default")
      (node (ref "U2") (pin "138") (pinfunction "ADC0_4/ADC1_4_138") (pintype "input"))
    )
    (net (code "116") (name "unconnected-(U2D-ADC0_5{slash}ADC1_5-Pad144)") (class "Default")
      (node (ref "U2") (pin "144") (pinfunction "ADC0_5/ADC1_5_144") (pintype "input"))
    )
    (net (code "117") (name "unconnected-(U2D-ADC0_6{slash}ADC1_6-Pad142)") (class "Default")
      (node (ref "U2") (pin "142") (pinfunction "ADC0_6/ADC1_6_142") (pintype "input"))
    )
    (net (code "118") (name "unconnected-(U2D-ADC0_7{slash}ADC1_7-Pad136)") (class "Default")
      (node (ref "U2") (pin "136") (pinfunction "ADC0_7/ADC1_7_136") (pintype "input"))
    )
    (net (code "119") (name "unconnected-(U2D-DBGEN-Pad28)") (class "Default")
      (node (ref "U2") (pin "28") (pinfunction "DBGEN_28") (pintype "input"))
    )
    (net (code "120") (name "unconnected-(U2D-RTCX1-Pad125)") (class "Default")
      (node (ref "U2") (pin "125") (pinfunction "RTCX1_125") (pintype "input"))
    )
    (net (code "121") (name "unconnected-(U2D-RTCX2-Pad126)") (class "Default")
      (node (ref "U2") (pin "126") (pinfunction "RTCX2_126") (pintype "output"))
    )
    (net (code "122") (name "unconnected-(U2D-RTC_ALARM-Pad129)") (class "Default")
      (node (ref "U2") (pin "129") (pinfunction "RTC_ALARM_129") (pintype "output"))
    )
    (net (code "123") (name "unconnected-(U2D-TCK{slash}SWDCLK-Pad27)") (class "Default")
      (node (ref "U2") (pin "27") (pinfunction "TCK/SWDCLK_27") (pintype "input"))
    )
    (net (code "124") (name "unconnected-(U2D-TDI-Pad26)") (class "Default")
      (node (ref "U2") (pin "26") (pinfunction "TDI_26") (pintype "input"))
    )
    (net (code "125") (name "unconnected-(U2D-TDO{slash}SWO-Pad31)") (class "Default")
      (node (ref "U2") (pin "31") (pinfunction "TDO/SWO_31") (pintype "output"))
    )
    (net (code "126") (name "unconnected-(U2D-TMS{slash}SWDIO-Pad30)") (class "Default")
      (node (ref "U2") (pin "30") (pinfunction "TMS/SWDIO_30") (pintype "input"))
    )
    (net (code "127") (name "unconnected-(U2D-USB0_RREF-Pad24)") (class "Default")
      (node (ref "U2") (pin "24") (pinfunction "USB0_RREF_24") (pintype "passive"))
    )
    (net (code "128") (name "unconnected-(U2D-~{TRST}-Pad29)") (class "Default")
      (node (ref "U2") (pin "29") (pinfunction "~{TRST}_29") (pintype "input"))
    )
    (net (code "129") (name "unconnected-(U9-NC-Pad2)") (class "Default")
      (node (ref "U9") (pin "2") (pinfunction "NC_2") (pintype "passive"))
    )
  )
)
